# mixer.net
KiCad netlist of a schematic drawn in Altium Designer
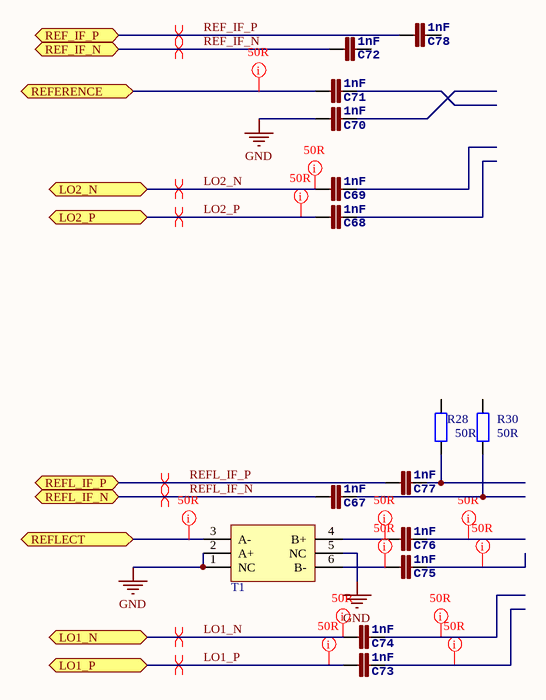
[diagram p0: mixer.SchDoc]

(export (version "E")
  (design (tool "Eeschema 10.0.6"))
  (components
    (comp (ref "C67")
      (value "1nF")
      (footprint "0402")
      (description "<b>Capacitor</b>\nStandard 0603 ceramic capacitor, and 0.1\" leaded capacitor.")
      (fields (field (name "PARTNO") "CC0402ZRY5V7BB104"))
      (libsource (lib "*") (part "CAP0402-CAP"))
    )
    (comp (ref "C68")
      (value "1nF")
      (footprint "0402")
      (description "<b>Capacitor</b>\nStandard 0603 ceramic capacitor, and 0.1\" leaded capacitor.")
      (fields (field (name "PARTNO") "CC0402ZRY5V7BB104"))
      (libsource (lib "*") (part "CAP0402-CAP"))
    )
    (comp (ref "C69")
      (value "1nF")
      (footprint "0402")
      (description "<b>Capacitor</b>\nStandard 0603 ceramic capacitor, and 0.1\" leaded capacitor.")
      (fields (field (name "PARTNO") "CC0402ZRY5V7BB104"))
      (libsource (lib "*") (part "CAP0402-CAP"))
    )
    (comp (ref "C70")
      (value "1nF")
      (footprint "0402")
      (description "<b>Capacitor</b>\nStandard 0603 ceramic capacitor, and 0.1\" leaded capacitor.")
      (fields (field (name "PARTNO") "CC0402ZRY5V7BB104"))
      (libsource (lib "*") (part "CAP0402-CAP"))
    )
    (comp (ref "C71")
      (value "1nF")
      (footprint "0402")
      (description "<b>Capacitor</b>\nStandard 0603 ceramic capacitor, and 0.1\" leaded capacitor.")
      (fields (field (name "PARTNO") "CC0402ZRY5V7BB104"))
      (libsource (lib "*") (part "CAP0402-CAP"))
    )
    (comp (ref "C72")
      (value "1nF")
      (footprint "0402")
      (description "<b>Capacitor</b>\nStandard 0603 ceramic capacitor, and 0.1\" leaded capacitor.")
      (fields (field (name "PARTNO") "CC0402ZRY5V7BB104"))
      (libsource (lib "*") (part "CAP0402-CAP"))
    )
    (comp (ref "C73")
      (value "1nF")
      (footprint "0402")
      (description "<b>Capacitor</b>\nStandard 0603 ceramic capacitor, and 0.1\" leaded capacitor.")
      (fields (field (name "PARTNO") "CC0402ZRY5V7BB104"))
      (libsource (lib "*") (part "CAP0402-CAP"))
    )
    (comp (ref "C74")
      (value "1nF")
      (footprint "0402")
      (description "<b>Capacitor</b>\nStandard 0603 ceramic capacitor, and 0.1\" leaded capacitor.")
      (fields (field (name "PARTNO") "CC0402ZRY5V7BB104"))
      (libsource (lib "*") (part "CAP0402-CAP"))
    )
    (comp (ref "C75")
      (value "1nF")
      (footprint "0402")
      (description "<b>Capacitor</b>\nStandard 0603 ceramic capacitor, and 0.1\" leaded capacitor.")
      (fields (field (name "PARTNO") "CC0402ZRY5V7BB104"))
      (libsource (lib "*") (part "CAP0402-CAP"))
    )
    (comp (ref "C76")
      (value "1nF")
      (footprint "0402")
      (description "<b>Capacitor</b>\nStandard 0603 ceramic capacitor, and 0.1\" leaded capacitor.")
      (fields (field (name "PARTNO") "CC0402ZRY5V7BB104"))
      (libsource (lib "*") (part "CAP0402-CAP"))
    )
    (comp (ref "C77")
      (value "1nF")
      (footprint "0402")
      (description "<b>Capacitor</b>\nStandard 0603 ceramic capacitor, and 0.1\" leaded capacitor.")
      (fields (field (name "PARTNO") "CC0402ZRY5V7BB104"))
      (libsource (lib "*") (part "CAP0402-CAP"))
    )
    (comp (ref "C78")
      (value "1nF")
      (footprint "0402")
      (description "<b>Capacitor</b>\nStandard 0603 ceramic capacitor, and 0.1\" leaded capacitor.")
      (fields (field (name "PARTNO") "CC0402ZRY5V7BB104"))
      (libsource (lib "*") (part "CAP0402-CAP"))
    )
    (comp (ref "R28")
      (value "50R")
      (footprint "0402")
      (description "Resistor")
      (fields (field (name "PUBLISHER") "Altium Limited"))
      (libsource (lib "RTC6705") (part "Res2"))
    )
    (comp (ref "R30")
      (value "50R")
      (footprint "0402")
      (description "Resistor")
      (fields (field (name "PUBLISHER") "Altium Limited"))
      (libsource (lib "RTC6705") (part "Res2"))
    )
    (comp (ref "T1")
      (value "TCM1-63AX+")
      (footprint "TCM1-63AX+")
      (libsource (lib "F4SDR") (part "TCM1-63AX+"))
    )
  )
  (nets
    (net (code "1") (name "/LO1_N") (class "Default")
      (node (ref "C74") (pin "1") (pinfunction "1_1") (pintype "passive"))
    )
    (net (code "2") (name "/LO1_P") (class "Default")
      (node (ref "C73") (pin "1") (pinfunction "1_1") (pintype "passive"))
    )
    (net (code "3") (name "/LO2_N") (class "Default")
      (node (ref "C69") (pin "1") (pinfunction "1_1") (pintype "passive"))
    )
    (net (code "4") (name "/LO2_P") (class "Default")
      (node (ref "C68") (pin "1") (pinfunction "1_1") (pintype "passive"))
    )
    (net (code "5") (name "/REFERENCE") (class "Default")
      (node (ref "C71") (pin "1") (pinfunction "1_1") (pintype "passive"))
    )
    (net (code "6") (name "/REFLECT") (class "Default")
      (node (ref "T1") (pin "3") (pinfunction "A-_3") (pintype "passive"))
    )
    (net (code "7") (name "/REFL_IF_N") (class "Default")
      (node (ref "C67") (pin "1") (pinfunction "1_1") (pintype "passive"))
    )
    (net (code "8") (name "/REFL_IF_P") (class "Default")
      (node (ref "C77") (pin "1") (pinfunction "1_1") (pintype "passive"))
    )
    (net (code "9") (name "/REF_IF_N") (class "Default")
      (node (ref "C72") (pin "1") (pinfunction "1_1") (pintype "passive"))
    )
    (net (code "10") (name "/REF_IF_P") (class "Default")
      (node (ref "C78") (pin "1") (pinfunction "1_1") (pintype "passive"))
    )
    (net (code "11") (name "GND") (class "Default")
      (node (ref "C70") (pin "1") (pinfunction "1_1") (pintype "passive"))
      (node (ref "T1") (pin "1") (pinfunction "NC_1") (pintype "passive"))
      (node (ref "T1") (pin "2") (pinfunction "A+_2") (pintype "passive"))
      (node (ref "T1") (pin "5") (pinfunction "NC_5") (pintype "passive"))
    )
    (net (code "12") (name "Net-(C67-Pad2)") (class "Default")
      (node (ref "C67") (pin "2") (pinfunction "2_2") (pintype "passive"))
      (node (ref "R30") (pin "1") (pinfunction "1_1") (pintype "passive"))
    )
    (net (code "13") (name "Net-(C77-Pad2)") (class "Default")
      (node (ref "C77") (pin "2") (pinfunction "2_2") (pintype "passive"))
      (node (ref "R28") (pin "1") (pinfunction "1_1") (pintype "passive"))
    )
    (net (code "14") (name "Net-(T1-B+)") (class "Default")
      (node (ref "C76") (pin "1") (pinfunction "1_1") (pintype "passive"))
      (node (ref "T1") (pin "4") (pinfunction "B+_4") (pintype "passive"))
    )
    (net (code "15") (name "Net-(T1-B-)") (class "Default")
      (node (ref "C75") (pin "1") (pinfunction "1_1") (pintype "passive"))
      (node (ref "T1") (pin "6") (pinfunction "B-_6") (pintype "passive"))
    )
    (net (code "16") (name "unconnected-(C68-Pad2)") (class "Default")
      (node (ref "C68") (pin "2") (pinfunction "2_2") (pintype "passive"))
    )
    (net (code "17") (name "unconnected-(C69-Pad2)") (class "Default")
      (node (ref "C69") (pin "2") (pinfunction "2_2") (pintype "passive"))
    )
    (net (code "18") (name "unconnected-(C70-Pad2)") (class "Default")
      (node (ref "C70") (pin "2") (pinfunction "2_2") (pintype "passive"))
    )
    (net (code "19") (name "unconnected-(C71-Pad2)") (class "Default")
      (node (ref "C71") (pin "2") (pinfunction "2_2") (pintype "passive"))
    )
    (net (code "20") (name "unconnected-(C72-Pad2)") (class "Default")
      (node (ref "C72") (pin "2") (pinfunction "2_2") (pintype "passive"))
    )
    (net (code "21") (name "unconnected-(C73-Pad2)") (class "Default")
      (node (ref "C73") (pin "2") (pinfunction "2_2") (pintype "passive"))
    )
    (net (code "22") (name "unconnected-(C74-Pad2)") (class "Default")
      (node (ref "C74") (pin "2") (pinfunction "2_2") (pintype "passive"))
    )
    (net (code "23") (name "unconnected-(C75-Pad2)") (class "Default")
      (node (ref "C75") (pin "2") (pinfunction "2_2") (pintype "passive"))
    )
    (net (code "24") (name "unconnected-(C76-Pad2)") (class "Default")
      (node (ref "C76") (pin "2") (pinfunction "2_2") (pintype "passive"))
    )
    (net (code "25") (name "unconnected-(C78-Pad2)") (class "Default")
      (node (ref "C78") (pin "2") (pinfunction "2_2") (pintype "passive"))
    )
    (net (code "26") (name "unconnected-(R28-Pad2)") (class "Default")
      (node (ref "R28") (pin "2") (pinfunction "2_2") (pintype "passive"))
    )
    (net (code "27") (name "unconnected-(R30-Pad2)") (class "Default")
      (node (ref "R30") (pin "2") (pinfunction "2_2") (pintype "passive"))
    )
  )
)
